# gpu.net
KiCad netlist of a schematic drawn in EAGLE
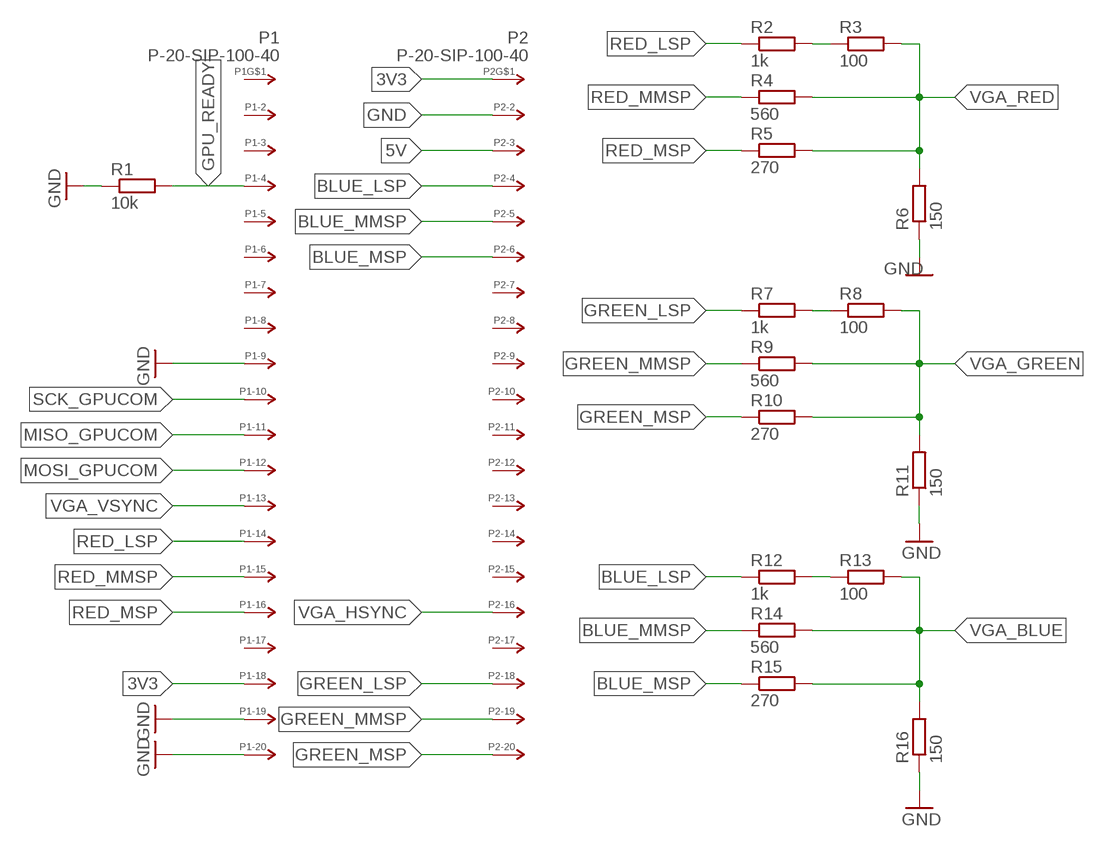
[diagram p0: schematic, sheet 1]

(export (version "E")
  (design (tool "Eeschema 10.0.6"))
  (components
    (comp (ref "P1")
      (value "P-20-SIP-100-40")
      (footprint "eagle-import:SIP-100-20-40")
      (libsource (lib "eagle-import") (part "P-20-SIP-100-40"))
    )
    (comp (ref "P2")
      (value "P-20-SIP-100-40")
      (footprint "eagle-import:SIP-100-20-40")
      (libsource (lib "eagle-import") (part "P-20-SIP-100-40"))
    )
    (comp (ref "R1")
      (value "10k")
      (footprint "eagle-import:R0805")
      (libsource (lib "eagle-import") (part "R-EU_R0805"))
    )
    (comp (ref "R2")
      (value "1k")
      (footprint "eagle-import:R0805")
      (libsource (lib "eagle-import") (part "R-EU_R0805"))
    )
    (comp (ref "R3")
      (value "100")
      (footprint "eagle-import:R0805")
      (libsource (lib "eagle-import") (part "R-EU_R0805"))
    )
    (comp (ref "R4")
      (value "560")
      (footprint "eagle-import:R0805")
      (libsource (lib "eagle-import") (part "R-EU_R0805"))
    )
    (comp (ref "R5")
      (value "270")
      (footprint "eagle-import:R0805")
      (libsource (lib "eagle-import") (part "R-EU_R0805"))
    )
    (comp (ref "R6")
      (value "150")
      (footprint "eagle-import:R0805")
      (libsource (lib "eagle-import") (part "R-EU_R0805"))
    )
    (comp (ref "R7")
      (value "1k")
      (footprint "eagle-import:R0805")
      (libsource (lib "eagle-import") (part "R-EU_R0805"))
    )
    (comp (ref "R8")
      (value "100")
      (footprint "eagle-import:R0805")
      (libsource (lib "eagle-import") (part "R-EU_R0805"))
    )
    (comp (ref "R9")
      (value "560")
      (footprint "eagle-import:R0805")
      (libsource (lib "eagle-import") (part "R-EU_R0805"))
    )
    (comp (ref "R10")
      (value "270")
      (footprint "eagle-import:R0805")
      (libsource (lib "eagle-import") (part "R-EU_R0805"))
    )
    (comp (ref "R11")
      (value "150")
      (footprint "eagle-import:R0805")
      (libsource (lib "eagle-import") (part "R-EU_R0805"))
    )
    (comp (ref "R12")
      (value "1k")
      (footprint "eagle-import:R0805")
      (libsource (lib "eagle-import") (part "R-EU_R0805"))
    )
    (comp (ref "R13")
      (value "100")
      (footprint "eagle-import:R0805")
      (libsource (lib "eagle-import") (part "R-EU_R0805"))
    )
    (comp (ref "R14")
      (value "560")
      (footprint "eagle-import:R0805")
      (libsource (lib "eagle-import") (part "R-EU_R0805"))
    )
    (comp (ref "R15")
      (value "270")
      (footprint "eagle-import:R0805")
      (libsource (lib "eagle-import") (part "R-EU_R0805"))
    )
    (comp (ref "R16")
      (value "150")
      (footprint "eagle-import:R0805")
      (libsource (lib "eagle-import") (part "R-EU_R0805"))
    )
  )
  (nets
    (net (code "1") (name "3V3") (class "Default")
      (node (ref "P1") (pin "18") (pinfunction "P_18") (pintype "passive"))
      (node (ref "P2") (pin "1") (pinfunction "P_1") (pintype "passive"))
    )
    (net (code "2") (name "5V") (class "Default")
      (node (ref "P2") (pin "3") (pinfunction "P_3") (pintype "passive"))
    )
    (net (code "3") (name "BLUE_LSP") (class "Default")
      (node (ref "P2") (pin "4") (pinfunction "P_4") (pintype "passive"))
      (node (ref "R12") (pin "1") (pinfunction "1_1") (pintype "passive"))
    )
    (net (code "4") (name "BLUE_MMSP") (class "Default")
      (node (ref "P2") (pin "5") (pinfunction "P_5") (pintype "passive"))
      (node (ref "R14") (pin "1") (pinfunction "1_1") (pintype "passive"))
    )
    (net (code "5") (name "BLUE_MSP") (class "Default")
      (node (ref "P2") (pin "6") (pinfunction "P_6") (pintype "passive"))
      (node (ref "R15") (pin "1") (pinfunction "1_1") (pintype "passive"))
    )
    (net (code "6") (name "GND") (class "Default")
      (node (ref "P1") (pin "19") (pinfunction "P_19") (pintype "passive"))
      (node (ref "P1") (pin "20") (pinfunction "P_20") (pintype "passive"))
      (node (ref "P1") (pin "9") (pinfunction "P_9") (pintype "passive"))
      (node (ref "P2") (pin "2") (pinfunction "P_2") (pintype "passive"))
      (node (ref "R1") (pin "1") (pinfunction "1_1") (pintype "passive"))
      (node (ref "R11") (pin "1") (pinfunction "1_1") (pintype "passive"))
      (node (ref "R16") (pin "1") (pinfunction "1_1") (pintype "passive"))
      (node (ref "R6") (pin "1") (pinfunction "1_1") (pintype "passive"))
    )
    (net (code "7") (name "GPU_READY") (class "Default")
      (node (ref "P1") (pin "4") (pinfunction "P_4") (pintype "passive"))
      (node (ref "R1") (pin "2") (pinfunction "2_2") (pintype "passive"))
    )
    (net (code "8") (name "GREEN_LSP") (class "Default")
      (node (ref "P2") (pin "18") (pinfunction "P_18") (pintype "passive"))
      (node (ref "R7") (pin "1") (pinfunction "1_1") (pintype "passive"))
    )
    (net (code "9") (name "GREEN_MMSP") (class "Default")
      (node (ref "P2") (pin "19") (pinfunction "P_19") (pintype "passive"))
      (node (ref "R9") (pin "1") (pinfunction "1_1") (pintype "passive"))
    )
    (net (code "10") (name "GREEN_MSP") (class "Default")
      (node (ref "P2") (pin "20") (pinfunction "P_20") (pintype "passive"))
      (node (ref "R10") (pin "1") (pinfunction "1_1") (pintype "passive"))
    )
    (net (code "11") (name "MISO_GPUCOM") (class "Default")
      (node (ref "P1") (pin "11") (pinfunction "P_11") (pintype "passive"))
    )
    (net (code "12") (name "MOSI_GPUCOM") (class "Default")
      (node (ref "P1") (pin "12") (pinfunction "P_12") (pintype "passive"))
    )
    (net (code "13") (name "Net-(R2-Pad2)") (class "Default")
      (node (ref "R2") (pin "2") (pinfunction "2_2") (pintype "passive"))
      (node (ref "R3") (pin "1") (pinfunction "1_1") (pintype "passive"))
    )
    (net (code "14") (name "Net-(R7-Pad2)") (class "Default")
      (node (ref "R7") (pin "2") (pinfunction "2_2") (pintype "passive"))
      (node (ref "R8") (pin "1") (pinfunction "1_1") (pintype "passive"))
    )
    (net (code "15") (name "Net-(R12-Pad2)") (class "Default")
      (node (ref "R12") (pin "2") (pinfunction "2_2") (pintype "passive"))
      (node (ref "R13") (pin "1") (pinfunction "1_1") (pintype "passive"))
    )
    (net (code "16") (name "RED_LSP") (class "Default")
      (node (ref "P1") (pin "14") (pinfunction "P_14") (pintype "passive"))
      (node (ref "R2") (pin "1") (pinfunction "1_1") (pintype "passive"))
    )
    (net (code "17") (name "RED_MMSP") (class "Default")
      (node (ref "P1") (pin "15") (pinfunction "P_15") (pintype "passive"))
      (node (ref "R4") (pin "1") (pinfunction "1_1") (pintype "passive"))
    )
    (net (code "18") (name "RED_MSP") (class "Default")
      (node (ref "P1") (pin "16") (pinfunction "P_16") (pintype "passive"))
      (node (ref "R5") (pin "1") (pinfunction "1_1") (pintype "passive"))
    )
    (net (code "19") (name "SCK_GPUCOM") (class "Default")
      (node (ref "P1") (pin "10") (pinfunction "P_10") (pintype "passive"))
    )
    (net (code "20") (name "VGA_BLUE") (class "Default")
      (node (ref "R13") (pin "2") (pinfunction "2_2") (pintype "passive"))
      (node (ref "R14") (pin "2") (pinfunction "2_2") (pintype "passive"))
      (node (ref "R15") (pin "2") (pinfunction "2_2") (pintype "passive"))
      (node (ref "R16") (pin "2") (pinfunction "2_2") (pintype "passive"))
    )
    (net (code "21") (name "VGA_GREEN") (class "Default")
      (node (ref "R10") (pin "2") (pinfunction "2_2") (pintype "passive"))
      (node (ref "R11") (pin "2") (pinfunction "2_2") (pintype "passive"))
      (node (ref "R8") (pin "2") (pinfunction "2_2") (pintype "passive"))
      (node (ref "R9") (pin "2") (pinfunction "2_2") (pintype "passive"))
    )
    (net (code "22") (name "VGA_HSYNC") (class "Default")
      (node (ref "P2") (pin "16") (pinfunction "P_16") (pintype "passive"))
    )
    (net (code "23") (name "VGA_RED") (class "Default")
      (node (ref "R3") (pin "2") (pinfunction "2_2") (pintype "passive"))
      (node (ref "R4") (pin "2") (pinfunction "2_2") (pintype "passive"))
      (node (ref "R5") (pin "2") (pinfunction "2_2") (pintype "passive"))
      (node (ref "R6") (pin "2") (pinfunction "2_2") (pintype "passive"))
    )
    (net (code "24") (name "VGA_VSYNC") (class "Default")
      (node (ref "P1") (pin "13") (pinfunction "P_13") (pintype "passive"))
    )
    (net (code "25") (name "unconnected-(P1H-P-Pad17)") (class "Default")
      (node (ref "P1") (pin "17") (pinfunction "P_17") (pintype "passive"))
    )
    (net (code "26") (name "unconnected-(P1K-P-Pad2)") (class "Default")
      (node (ref "P1") (pin "2") (pinfunction "P_2") (pintype "passive"))
    )
    (net (code "27") (name "unconnected-(P1M-P-Pad3)") (class "Default")
      (node (ref "P1") (pin "3") (pinfunction "P_3") (pintype "passive"))
    )
    (net (code "28") (name "unconnected-(P1O-P-Pad5)") (class "Default")
      (node (ref "P1") (pin "5") (pinfunction "P_5") (pintype "passive"))
    )
    (net (code "29") (name "unconnected-(P1P-P-Pad6)") (class "Default")
      (node (ref "P1") (pin "6") (pinfunction "P_6") (pintype "passive"))
    )
    (net (code "30") (name "unconnected-(P1Q-P-Pad7)") (class "Default")
      (node (ref "P1") (pin "7") (pinfunction "P_7") (pintype "passive"))
    )
    (net (code "31") (name "unconnected-(P1R-P-Pad8)") (class "Default")
      (node (ref "P1") (pin "8") (pinfunction "P_8") (pintype "passive"))
    )
    (net (code "32") (name "unconnected-(P1T-P-Pad1)") (class "Default")
      (node (ref "P1") (pin "1") (pinfunction "P_1") (pintype "passive"))
    )
    (net (code "33") (name "unconnected-(P2A-P-Pad10)") (class "Default")
      (node (ref "P2") (pin "10") (pinfunction "P_10") (pintype "passive"))
    )
    (net (code "34") (name "unconnected-(P2B-P-Pad11)") (class "Default")
      (node (ref "P2") (pin "11") (pinfunction "P_11") (pintype "passive"))
    )
    (net (code "35") (name "unconnected-(P2C-P-Pad12)") (class "Default")
      (node (ref "P2") (pin "12") (pinfunction "P_12") (pintype "passive"))
    )
    (net (code "36") (name "unconnected-(P2D-P-Pad13)") (class "Default")
      (node (ref "P2") (pin "13") (pinfunction "P_13") (pintype "passive"))
    )
    (net (code "37") (name "unconnected-(P2E-P-Pad14)") (class "Default")
      (node (ref "P2") (pin "14") (pinfunction "P_14") (pintype "passive"))
    )
    (net (code "38") (name "unconnected-(P2F-P-Pad15)") (class "Default")
      (node (ref "P2") (pin "15") (pinfunction "P_15") (pintype "passive"))
    )
    (net (code "39") (name "unconnected-(P2H-P-Pad17)") (class "Default")
      (node (ref "P2") (pin "17") (pinfunction "P_17") (pintype "passive"))
    )
    (net (code "40") (name "unconnected-(P2Q-P-Pad7)") (class "Default")
      (node (ref "P2") (pin "7") (pinfunction "P_7") (pintype "passive"))
    )
    (net (code "41") (name "unconnected-(P2R-P-Pad8)") (class "Default")
      (node (ref "P2") (pin "8") (pinfunction "P_8") (pintype "passive"))
    )
    (net (code "42") (name "unconnected-(P2S-P-Pad9)") (class "Default")
      (node (ref "P2") (pin "9") (pinfunction "P_9") (pintype "passive"))
    )
  )
)
